# MIC_Headphone.net
KiCad netlist of a schematic drawn in Altium Designer
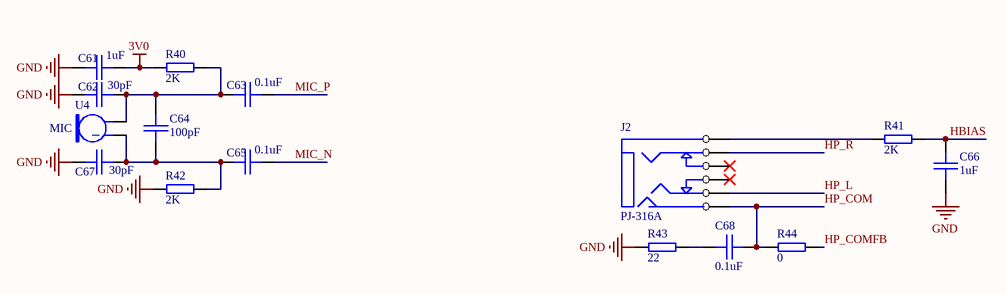
[diagram p0: MIC&Headphone.SchDoc]

(export (version "E")
  (design (tool "Eeschema 10.0.6"))
  (components
    (comp (ref "C61")
      (value "1uF")
      (footprint "CAP-0603")
      (description "陶瓷贴片电容0603")
      (fields (field (name "TOLERANCE") "10%") (field (name "VOLTAGE") "50V"))
      (libsource (lib "momo") (part "C_0603"))
    )
    (comp (ref "C62")
      (value "30pF")
      (footprint "CAP-0603")
      (description "陶瓷贴片电容0603")
      (fields (field (name "TOLERANCE") "10%") (field (name "VOLTAGE") "50V"))
      (libsource (lib "momo") (part "C_0603"))
    )
    (comp (ref "C63")
      (value "0.1uF")
      (footprint "CAP-0603")
      (description "陶瓷贴片电容0603")
      (fields (field (name "TOLERANCE") "10%") (field (name "VOLTAGE") "50V"))
      (libsource (lib "momo") (part "C_0603"))
    )
    (comp (ref "C64")
      (value "100pF")
      (footprint "CAP-0603")
      (description "陶瓷贴片电容0603")
      (fields (field (name "TOLERANCE") "10%") (field (name "VOLTAGE") "50V"))
      (libsource (lib "momo") (part "C_0603"))
    )
    (comp (ref "C65")
      (value "0.1uF")
      (footprint "CAP-0603")
      (description "陶瓷贴片电容0603")
      (fields (field (name "TOLERANCE") "10%") (field (name "VOLTAGE") "50V"))
      (libsource (lib "momo") (part "C_0603"))
    )
    (comp (ref "C66")
      (value "1uF")
      (footprint "CAP-0603")
      (description "陶瓷贴片电容0603")
      (fields (field (name "TOLERANCE") "10%") (field (name "VOLTAGE") "50V"))
      (libsource (lib "momo") (part "C_0603"))
    )
    (comp (ref "C67")
      (value "30pF")
      (footprint "CAP-0603")
      (description "陶瓷贴片电容0603")
      (fields (field (name "TOLERANCE") "10%") (field (name "VOLTAGE") "50V"))
      (libsource (lib "momo") (part "C_0603"))
    )
    (comp (ref "C68")
      (value "0.1uF")
      (footprint "CAP-0603")
      (description "陶瓷贴片电容0603")
      (fields (field (name "TOLERANCE") "10%") (field (name "VOLTAGE") "50V"))
      (libsource (lib "momo") (part "C_0603"))
    )
    (comp (ref "J2")
      (value "PJ-316A")
      (footprint "PJ-316A")
      (description "音频接口，左右声道+麦克")
      (libsource (lib "momo") (part "PJ-316A"))
    )
    (comp (ref "R40")
      (value "2K")
      (footprint "RES-0603")
      (description "贴片电阻0603")
      (fields (field (name "TOLERANCE") "5%") (field (name "VOLTAGE") "50V"))
      (libsource (lib "momo") (part "R_0603"))
    )
    (comp (ref "R41")
      (value "2K")
      (footprint "RES-0603")
      (description "贴片电阻0603")
      (fields (field (name "TOLERANCE") "5%") (field (name "VOLTAGE") "50V"))
      (libsource (lib "momo") (part "R_0603"))
    )
    (comp (ref "R42")
      (value "2K")
      (footprint "RES-0603")
      (description "贴片电阻0603")
      (fields (field (name "TOLERANCE") "5%") (field (name "VOLTAGE") "50V"))
      (libsource (lib "momo") (part "R_0603"))
    )
    (comp (ref "R43")
      (value "22")
      (footprint "RES-0603")
      (description "贴片电阻0603")
      (fields (field (name "TOLERANCE") "5%") (field (name "VOLTAGE") "50V"))
      (libsource (lib "momo") (part "R_0603"))
    )
    (comp (ref "R44")
      (value "0")
      (footprint "RES-0603")
      (description "贴片电阻0603")
      (fields (field (name "TOLERANCE") "5%") (field (name "VOLTAGE") "50V"))
      (libsource (lib "momo") (part "R_0603"))
    )
    (comp (ref "U4")
      (value "MIC")
      (footprint "MIC_9767")
      (description "咪头")
      (libsource (lib "momo") (part "MIC"))
    )
  )
  (nets
    (net (code "1") (name "/HBIAS") (class "Default")
      (node (ref "C66") (pin "2") (pinfunction "2_2") (pintype "passive"))
      (node (ref "R41") (pin "2") (pinfunction "2_2") (pintype "passive"))
    )
    (net (code "2") (name "/HP_COM") (class "Default")
      (node (ref "C68") (pin "2") (pinfunction "2_2") (pintype "passive"))
      (node (ref "J2") (pin "4") (pinfunction "MIC_4") (pintype "passive"))
      (node (ref "R44") (pin "1") (pinfunction "1_1") (pintype "passive"))
    )
    (net (code "3") (name "/HP_COMFB") (class "Default")
      (node (ref "R44") (pin "2") (pinfunction "2_2") (pintype "passive"))
    )
    (net (code "4") (name "/HP_L") (class "Default")
      (node (ref "J2") (pin "2") (pinfunction "L_2") (pintype "passive"))
    )
    (net (code "5") (name "/HP_R") (class "Default")
      (node (ref "J2") (pin "3") (pinfunction "R_3") (pintype "passive"))
    )
    (net (code "6") (name "/MIC_N") (class "Default")
      (node (ref "C65") (pin "2") (pinfunction "2_2") (pintype "passive"))
    )
    (net (code "7") (name "/MIC_P") (class "Default")
      (node (ref "C63") (pin "2") (pinfunction "2_2") (pintype "passive"))
    )
    (net (code "8") (name "3V0") (class "Default")
      (node (ref "C61") (pin "2") (pinfunction "2_2") (pintype "passive"))
      (node (ref "R40") (pin "1") (pinfunction "1_1") (pintype "passive"))
    )
    (net (code "9") (name "GND") (class "Default")
      (node (ref "C61") (pin "1") (pinfunction "1_1") (pintype "passive"))
      (node (ref "C62") (pin "1") (pinfunction "1_1") (pintype "passive"))
      (node (ref "C66") (pin "1") (pinfunction "1_1") (pintype "passive"))
      (node (ref "C67") (pin "1") (pinfunction "1_1") (pintype "passive"))
      (node (ref "R42") (pin "1") (pinfunction "1_1") (pintype "passive"))
      (node (ref "R43") (pin "1") (pinfunction "1_1") (pintype "passive"))
    )
    (net (code "10") (name "Net-(C62-Pad2)") (class "Default")
      (node (ref "C62") (pin "2") (pinfunction "2_2") (pintype "passive"))
      (node (ref "C63") (pin "1") (pinfunction "1_1") (pintype "passive"))
      (node (ref "C64") (pin "2") (pinfunction "2_2") (pintype "passive"))
      (node (ref "R40") (pin "2") (pinfunction "2_2") (pintype "passive"))
      (node (ref "U4") (pin "2") (pinfunction "2_2") (pintype "passive"))
    )
    (net (code "11") (name "Net-(C64-Pad1)") (class "Default")
      (node (ref "C64") (pin "1") (pinfunction "1_1") (pintype "passive"))
      (node (ref "C65") (pin "1") (pinfunction "1_1") (pintype "passive"))
      (node (ref "C67") (pin "2") (pinfunction "2_2") (pintype "passive"))
      (node (ref "R42") (pin "2") (pinfunction "2_2") (pintype "passive"))
      (node (ref "U4") (pin "1") (pinfunction "1_1") (pintype "passive"))
    )
    (net (code "12") (name "Net-(C68-Pad1)") (class "Default")
      (node (ref "C68") (pin "1") (pinfunction "1_1") (pintype "passive"))
      (node (ref "R43") (pin "2") (pinfunction "2_2") (pintype "passive"))
    )
    (net (code "13") (name "Net-(J2-GND)") (class "Default")
      (node (ref "J2") (pin "1") (pinfunction "GND_1") (pintype "passive"))
      (node (ref "R41") (pin "1") (pinfunction "1_1") (pintype "passive"))
    )
    (net (code "14") (name "unconnected-(J2-L_DET-Pad5)") (class "Default")
      (node (ref "J2") (pin "5") (pinfunction "L_DET_5") (pintype "passive+no_connect"))
    )
    (net (code "15") (name "unconnected-(J2-R_DET-Pad6)") (class "Default")
      (node (ref "J2") (pin "6") (pinfunction "R_DET_6") (pintype "passive+no_connect"))
    )
  )
)
